# design.net
KiCad netlist of a schematic drawn in Altium Designer
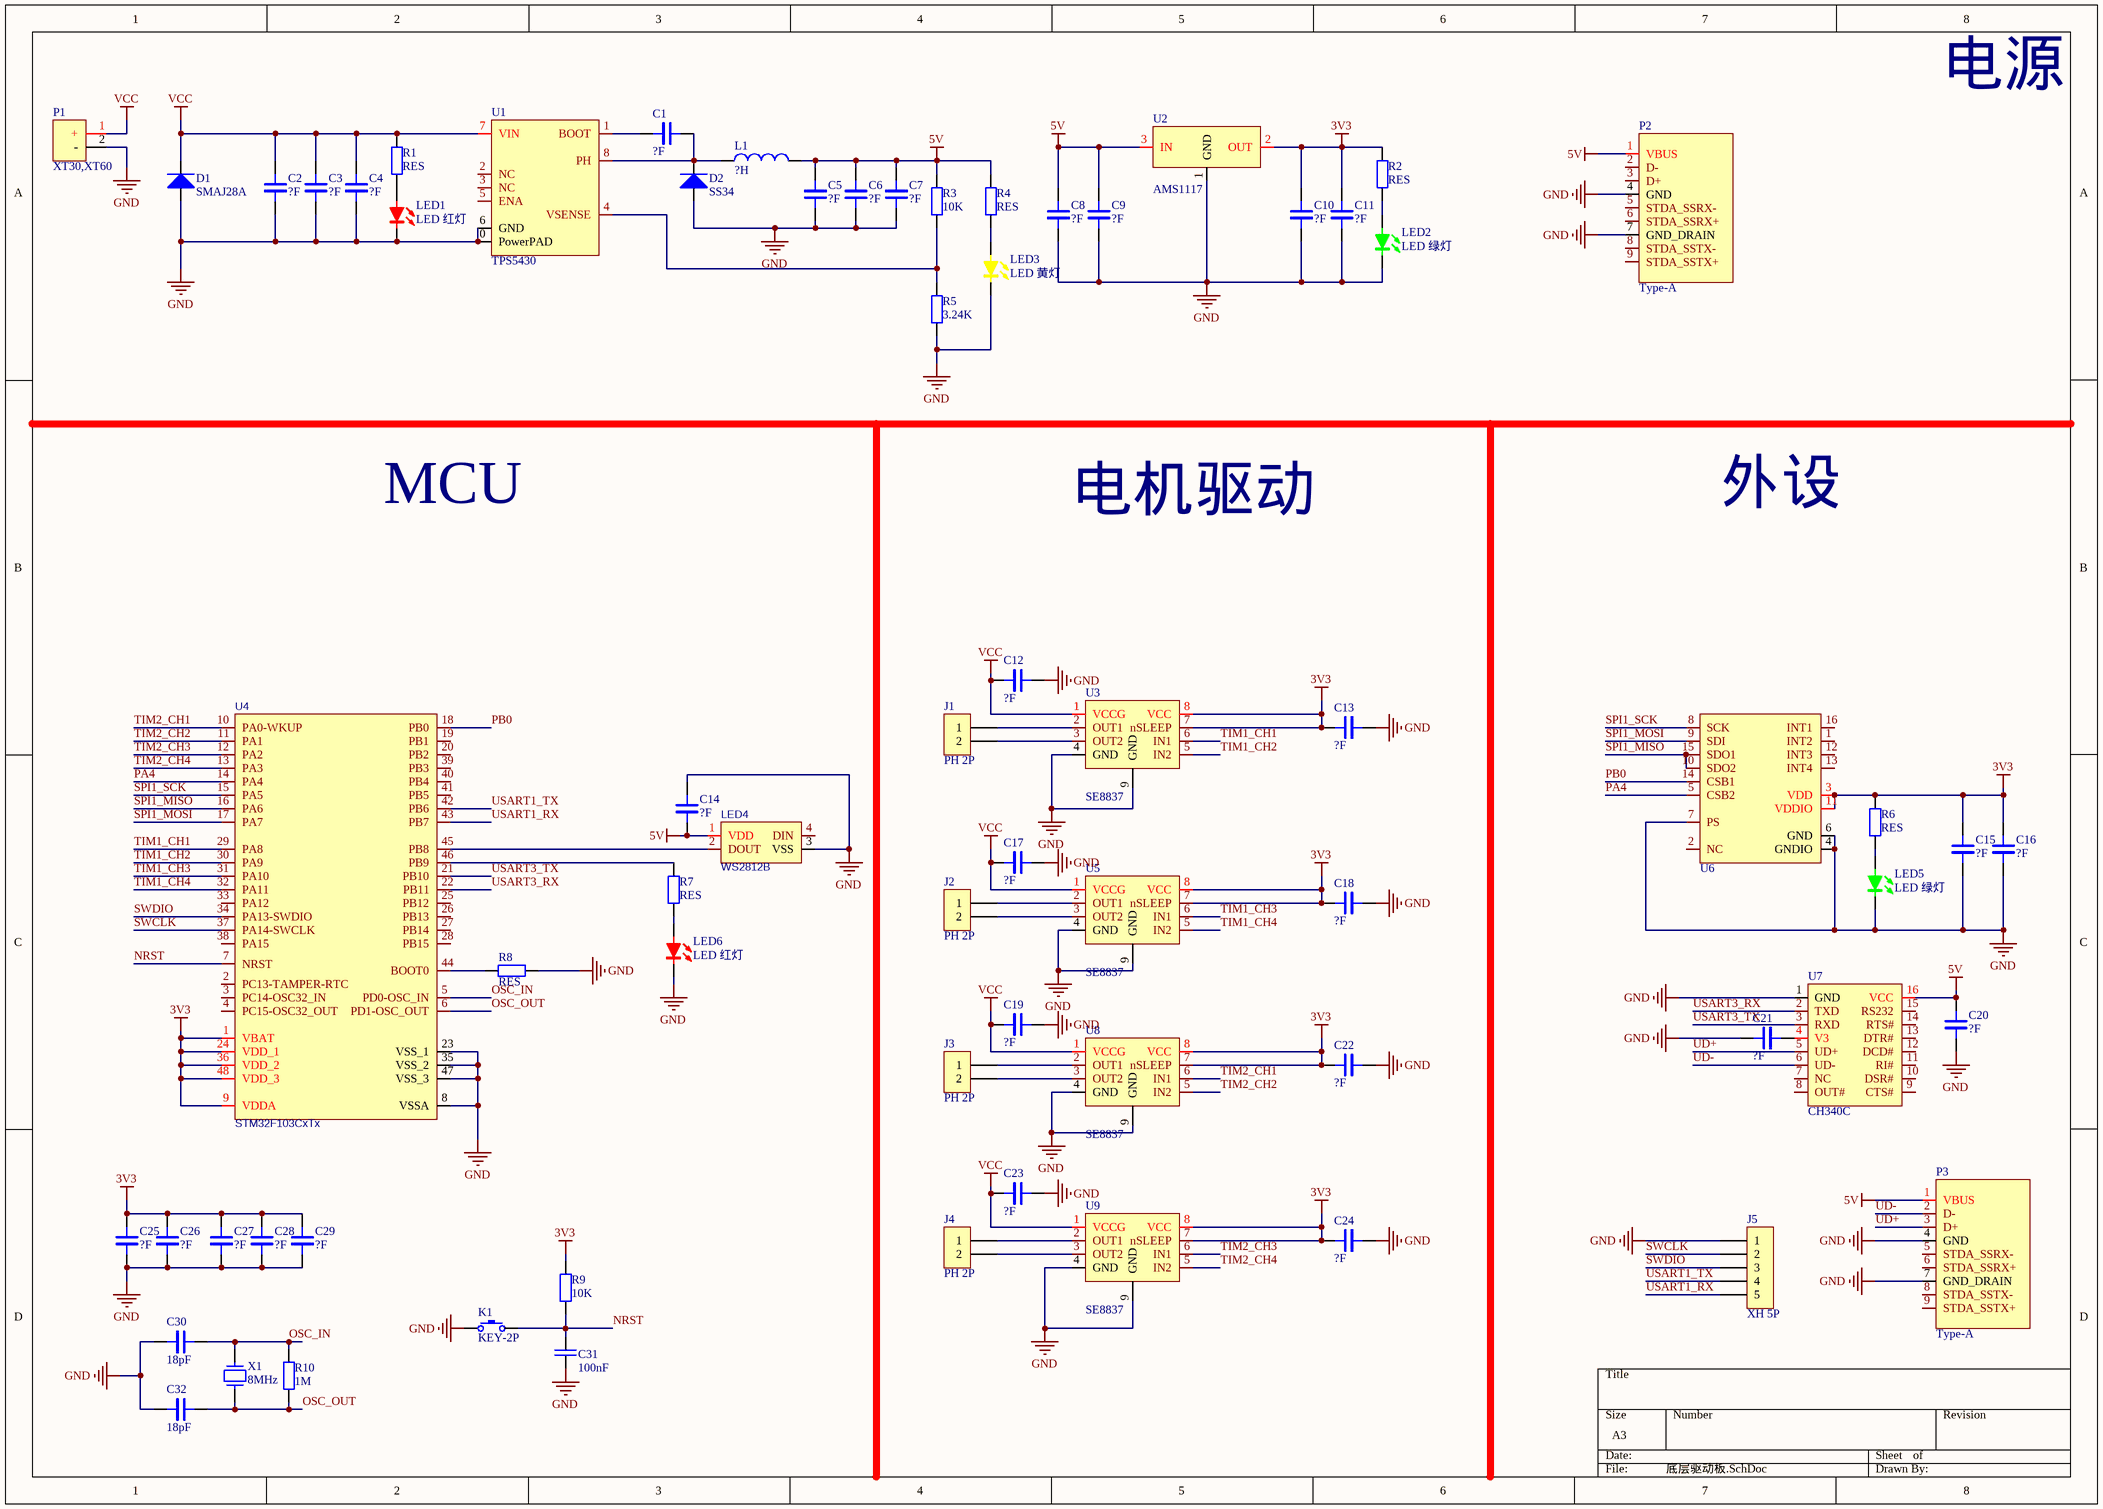
[diagram p0: 底层驱动板.SchDoc]

(export (version "E")
  (design (tool "Eeschema 10.0.6"))
  (components
    (comp (ref "C1")
      (value "?F")
      (footprint "C 0603")
      (description "Capacitor")
      (libsource (lib "General") (part "CAP"))
    )
    (comp (ref "C2")
      (value "?F")
      (footprint "C 1206")
      (description "Capacitor")
      (libsource (lib "General") (part "CAP"))
    )
    (comp (ref "C3")
      (value "?F")
      (footprint "C 1206")
      (description "Capacitor")
      (libsource (lib "General") (part "CAP"))
    )
    (comp (ref "C4")
      (value "?F")
      (footprint "C 0603")
      (description "Capacitor")
      (libsource (lib "General") (part "CAP"))
    )
    (comp (ref "C5")
      (value "?F")
      (footprint "C 1206")
      (description "Capacitor")
      (libsource (lib "General（旧）") (part "CAP"))
    )
    (comp (ref "C6")
      (value "?F")
      (footprint "C 1206")
      (description "Capacitor")
      (libsource (lib "General（旧）") (part "CAP"))
    )
    (comp (ref "C7")
      (value "?F")
      (footprint "C 0603")
      (description "Capacitor")
      (libsource (lib "General") (part "CAP"))
    )
    (comp (ref "C8")
      (value "?F")
      (footprint "C 1206")
      (description "Capacitor")
      (libsource (lib "General（旧）") (part "CAP"))
    )
    (comp (ref "C9")
      (value "?F")
      (footprint "C 1206")
      (description "Capacitor")
      (libsource (lib "General（旧）") (part "CAP"))
    )
    (comp (ref "C10")
      (value "?F")
      (footprint "C 1206")
      (description "Capacitor")
      (libsource (lib "General（旧）") (part "CAP"))
    )
    (comp (ref "C11")
      (value "?F")
      (footprint "C 1206")
      (description "Capacitor")
      (libsource (lib "General（旧）") (part "CAP"))
    )
    (comp (ref "C12")
      (value "?F")
      (footprint "C 1206")
      (description "Capacitor")
      (libsource (lib "General") (part "CAP"))
    )
    (comp (ref "C13")
      (value "?F")
      (footprint "C 0603")
      (description "Capacitor")
      (libsource (lib "General") (part "CAP"))
    )
    (comp (ref "C14")
      (value "?F")
      (footprint "C 0603")
      (description "Capacitor")
      (libsource (lib "General") (part "CAP"))
    )
    (comp (ref "C15")
      (value "?F")
      (footprint "C 0603")
      (description "Capacitor")
      (libsource (lib "General") (part "CAP"))
    )
    (comp (ref "C16")
      (value "?F")
      (footprint "C 0603")
      (description "Capacitor")
      (libsource (lib "General") (part "CAP"))
    )
    (comp (ref "C17")
      (value "?F")
      (footprint "C 1206")
      (description "Capacitor")
      (libsource (lib "General") (part "CAP"))
    )
    (comp (ref "C18")
      (value "?F")
      (footprint "C 0603")
      (description "Capacitor")
      (libsource (lib "General") (part "CAP"))
    )
    (comp (ref "C19")
      (value "?F")
      (footprint "C 1206")
      (description "Capacitor")
      (libsource (lib "General") (part "CAP"))
    )
    (comp (ref "C20")
      (value "?F")
      (footprint "C 0603")
      (description "Capacitor")
      (libsource (lib "General") (part "CAP"))
    )
    (comp (ref "C21")
      (value "?F")
      (footprint "C 0603")
      (description "Capacitor")
      (libsource (lib "General") (part "CAP"))
    )
    (comp (ref "C22")
      (value "?F")
      (footprint "C 0603")
      (description "Capacitor")
      (libsource (lib "General") (part "CAP"))
    )
    (comp (ref "C23")
      (value "?F")
      (footprint "C 1206")
      (description "Capacitor")
      (libsource (lib "General") (part "CAP"))
    )
    (comp (ref "C24")
      (value "?F")
      (footprint "C 0603")
      (description "Capacitor")
      (libsource (lib "General") (part "CAP"))
    )
    (comp (ref "C25")
      (value "?F")
      (footprint "C 0603")
      (description "Capacitor")
      (libsource (lib "General") (part "CAP"))
    )
    (comp (ref "C26")
      (value "?F")
      (footprint "C 0603")
      (description "Capacitor")
      (libsource (lib "General") (part "CAP"))
    )
    (comp (ref "C27")
      (value "?F")
      (footprint "C 0603")
      (description "Capacitor")
      (libsource (lib "General") (part "CAP"))
    )
    (comp (ref "C28")
      (value "?F")
      (footprint "C 0603")
      (description "Capacitor")
      (libsource (lib "General") (part "CAP"))
    )
    (comp (ref "C29")
      (value "?F")
      (footprint "C 0603")
      (description "Capacitor")
      (libsource (lib "General") (part "CAP"))
    )
    (comp (ref "C30")
      (value "18pF")
      (footprint "C 0603")
      (description "Capacitor")
      (libsource (lib "General") (part "CAP"))
    )
    (comp (ref "C31")
      (value "100nF")
      (footprint "C 0603")
      (fields (field (name "PUBLISHER") "Altium Limited"))
      (libsource (lib "电容-电阻-电感") (part "Cap"))
    )
    (comp (ref "C32")
      (value "18pF")
      (footprint "C 0603")
      (description "Capacitor")
      (libsource (lib "General") (part "CAP"))
    )
    (comp (ref "D1")
      (value "SMAJ28A")
      (footprint "SMA")
      (description "TVS")
      (libsource (lib "General") (part "SMAJ28A"))
    )
    (comp (ref "D2")
      (value "SS34")
      (footprint "SMA")
      (description "肖特基二极管")
      (fields
        (field (name "BOM_SUPPLIER PART") "C431540")
        (field (name "BOM_MANUFACTURER PART") "MSK12C02")
        (field (name "CONTRIBUTOR") "LCSC")
      )
      (libsource (lib "General") (part "SS34"))
    )
    (comp (ref "J1")
      (value "PH 2P")
      (footprint "PH2.0 S-W-2P")
      (description "Connector")
      (libsource (lib "General") (part "PH 2P"))
    )
    (comp (ref "J2")
      (value "PH 2P")
      (footprint "PH2.0 S-W-2P")
      (description "Connector")
      (libsource (lib "General") (part "PH 2P"))
    )
    (comp (ref "J3")
      (value "PH 2P")
      (footprint "PH2.0 S-W-2P")
      (description "Connector")
      (libsource (lib "General") (part "PH 2P"))
    )
    (comp (ref "J4")
      (value "PH 2P")
      (footprint "PH2.0 S-W-2P")
      (description "Connector")
      (libsource (lib "General") (part "PH 2P"))
    )
    (comp (ref "J5")
      (value "XH 5P")
      (footprint "XH2.54-5P_H")
      (description "Connector")
      (libsource (lib "General") (part "XH 5P"))
    )
    (comp (ref "K1")
      (value "KEY-2P")
      (footprint "*SW-按键")
      (description "Key")
      (libsource (lib "General") (part "KEY-2P"))
    )
    (comp (ref "L1")
      (value "?H")
      (footprint "SMD 7*7*4")
      (description "Inductor")
      (fields (field (name "PUBLISHER") "Altium Limited"))
      (libsource (lib "General") (part "Inductor"))
    )
    (comp (ref "LED1")
      (value "LED 红灯")
      (footprint "LED 0603-R")
      (description "LED")
      (libsource (lib "General") (part "LED 红灯"))
    )
    (comp (ref "LED2")
      (value "LED 绿灯")
      (footprint "LED 0603-G")
      (description "LED")
      (libsource (lib "General") (part "LED 绿灯"))
    )
    (comp (ref "LED3")
      (value "LED 黄灯")
      (footprint "LED 0603-Y")
      (description "LED")
      (libsource (lib "General") (part "LED 黄灯"))
    )
    (comp (ref "LED4")
      (value "WS2812B")
      (footprint "*WS2812B-3535")
      (description "可控RGB灯")
      (fields
        (field (name "BOM_MANUFACTURER PART") "WS2812B-3535")
        (field (name "BOM_SUPPLIER PART") "C114583")
        (field (name "CONTRIBUTOR") "LCSC")
      )
      (libsource (lib "General") (part "WS2812B"))
    )
    (comp (ref "LED5")
      (value "LED 绿灯")
      (footprint "LED 0603-G")
      (description "LED")
      (libsource (lib "General") (part "LED 绿灯"))
    )
    (comp (ref "LED6")
      (value "LED 红灯")
      (footprint "LED 0603-R")
      (description "LED")
      (libsource (lib "General") (part "LED 红灯"))
    )
    (comp (ref "P1")
      (value "XT30,XT60")
      (footprint "*XT30PW-M")
      (description "电源接口")
      (libsource (lib "General") (part "XT"))
    )
    (comp (ref "P2")
      (value "Type-A")
      (footprint "*Type-A 母 弯插")
      (description "USB连接器")
      (libsource (lib "General") (part "Type-A"))
    )
    (comp (ref "P3")
      (value "Type-A")
      (footprint "*Type-A 母 弯插")
      (description "USB连接器")
      (libsource (lib "General") (part "Type-A"))
    )
    (comp (ref "R1")
      (value "RES")
      (footprint "R 0603")
      (description "Resistor")
      (libsource (lib "") (part "RES_1"))
    )
    (comp (ref "R2")
      (value "RES")
      (footprint "R 0603")
      (description "Resistor")
      (libsource (lib "General（旧）") (part "RES"))
    )
    (comp (ref "R3")
      (value "10K")
      (footprint "R 0603")
      (description "Resistor")
      (libsource (lib "General（旧）") (part "RES"))
    )
    (comp (ref "R4")
      (value "RES")
      (footprint "R 0603")
      (description "Resistor")
      (libsource (lib "General（旧）") (part "RES"))
    )
    (comp (ref "R5")
      (value "3.24K")
      (footprint "R 0603")
      (description "Resistor")
      (libsource (lib "General（旧）") (part "RES"))
    )
    (comp (ref "R6")
      (value "RES")
      (footprint "R 0603")
      (description "Resistor")
      (libsource (lib "") (part "RES_1"))
    )
    (comp (ref "R7")
      (value "RES")
      (footprint "R 0603")
      (description "Resistor")
      (libsource (lib "General") (part "RES"))
    )
    (comp (ref "R8")
      (value "RES")
      (footprint "R 0603")
      (description "Resistor")
      (libsource (lib "") (part "RES_2"))
    )
    (comp (ref "R9")
      (value "10K")
      (footprint "R 0603")
      (fields (field (name "PUBLISHER") "Altium Limited"))
      (libsource (lib "电容-电阻-电感") (part "Res"))
    )
    (comp (ref "R10")
      (value "1M")
      (footprint "R 0603")
      (description "Resistor")
      (libsource (lib "General") (part "RES"))
    )
    (comp (ref "U1")
      (value "TPS5430")
      (footprint "SOP8-EP")
      (description "DC-DC 降压芯片")
      (libsource (lib "General") (part "TPS5450"))
    )
    (comp (ref "U2")
      (value "AMS1117")
      (footprint "SOT223")
      (description "LDO")
      (libsource (lib "General（旧）") (part "AMS1117"))
    )
    (comp (ref "U3")
      (value "SE8837")
      (footprint "*DFN-8-EP")
      (description "电机驱动芯片")
      (libsource (lib "General") (part "SE8837"))
    )
    (comp (ref "U4")
      (value "STM32F103CxTx")
      (footprint "LQFP48 7X7")
      (description "STM32单片机")
      (fields
        (field (name "BOM_MANUFACTURER PART") "STM32F103C8T6")
        (field (name "BOM_SUPPLIER PART") "C8734")
      )
      (libsource (lib "General") (part "STM32F103CxTx"))
    )
    (comp (ref "U5")
      (value "SE8837")
      (footprint "*DFN-8-EP")
      (description "电机驱动芯片")
      (libsource (lib "General") (part "SE8837"))
    )
    (comp (ref "U6")
      (value "BMI088")
      (footprint "*LGA-16")
      (description "陀螺仪")
      (libsource (lib "General") (part "BMI088"))
    )
    (comp (ref "U7")
      (value "CH340C")
      (footprint "SOP16")
      (description "USB转串口芯片")
      (fields
        (field (name "BOM_SUPPLIER PART") "C431540")
        (field (name "BOM_MANUFACTURER PART") "MSK12C02")
        (field (name "CONTRIBUTOR") "LCSC")
      )
      (libsource (lib "General") (part "CH340C"))
    )
    (comp (ref "U8")
      (value "SE8837")
      (footprint "*DFN-8-EP")
      (description "电机驱动芯片")
      (libsource (lib "General") (part "SE8837"))
    )
    (comp (ref "U9")
      (value "SE8837")
      (footprint "*DFN-8-EP")
      (description "电机驱动芯片")
      (libsource (lib "General") (part "SE8837"))
    )
    (comp (ref "X1")
      (value "8MHz")
      (footprint "XTAL SMD-2P")
      (description "Oscillator")
      (libsource (lib "General") (part "XTAL"))
    )
  )
  (nets
    (net (code "1") (name "/NRST") (class "Default")
      (node (ref "C31") (pin "1") (pinfunction "1_1") (pintype "passive"))
      (node (ref "K1") (pin "2") (pinfunction "2_2") (pintype "passive"))
      (node (ref "R9") (pin "1") (pinfunction "1_1") (pintype "passive"))
      (node (ref "U4") (pin "7") (pinfunction "NRST_7") (pintype "passive"))
    )
    (net (code "2") (name "/OSC_IN") (class "Default")
      (node (ref "C30") (pin "2") (pinfunction "2_2") (pintype "passive"))
      (node (ref "R10") (pin "1") (pinfunction "1_1") (pintype "passive"))
      (node (ref "U4") (pin "5") (pinfunction "PD0-OSC_IN_5") (pintype "passive"))
      (node (ref "X1") (pin "1") (pinfunction "1_1") (pintype "passive"))
    )
    (net (code "3") (name "/OSC_OUT") (class "Default")
      (node (ref "C32") (pin "2") (pinfunction "2_2") (pintype "passive"))
      (node (ref "R10") (pin "2") (pinfunction "2_2") (pintype "passive"))
      (node (ref "U4") (pin "6") (pinfunction "PD1-OSC_OUT_6") (pintype "passive"))
      (node (ref "X1") (pin "2") (pinfunction "2_2") (pintype "passive"))
    )
    (net (code "4") (name "/PA4") (class "Default")
      (node (ref "U4") (pin "14") (pinfunction "PA4_14") (pintype "passive"))
      (node (ref "U6") (pin "5") (pinfunction "CSB2_5") (pintype "passive"))
    )
    (net (code "5") (name "/PB0") (class "Default")
      (node (ref "U4") (pin "18") (pinfunction "PB0_18") (pintype "passive"))
      (node (ref "U6") (pin "14") (pinfunction "CSB1_14") (pintype "passive"))
    )
    (net (code "6") (name "/SPI1_MISO") (class "Default")
      (node (ref "U4") (pin "16") (pinfunction "PA6_16") (pintype "passive"))
      (node (ref "U6") (pin "10") (pinfunction "SDO2_10") (pintype "passive"))
      (node (ref "U6") (pin "15") (pinfunction "SDO1_15") (pintype "passive"))
    )
    (net (code "7") (name "/SPI1_MOSI") (class "Default")
      (node (ref "U4") (pin "17") (pinfunction "PA7_17") (pintype "passive"))
      (node (ref "U6") (pin "9") (pinfunction "SDI_9") (pintype "passive"))
    )
    (net (code "8") (name "/SPI1_SCK") (class "Default")
      (node (ref "U4") (pin "15") (pinfunction "PA5_15") (pintype "passive"))
      (node (ref "U6") (pin "8") (pinfunction "SCK_8") (pintype "passive"))
    )
    (net (code "9") (name "/SWCLK") (class "Default")
      (node (ref "J5") (pin "2") (pinfunction "2_2") (pintype "passive"))
      (node (ref "U4") (pin "37") (pinfunction "PA14-SWCLK_37") (pintype "passive"))
    )
    (net (code "10") (name "/SWDIO") (class "Default")
      (node (ref "J5") (pin "3") (pinfunction "3_3") (pintype "passive"))
      (node (ref "U4") (pin "34") (pinfunction "PA13-SWDIO_34") (pintype "passive"))
    )
    (net (code "11") (name "/TIM1_CH1") (class "Default")
      (node (ref "U3") (pin "6") (pinfunction "IN1_6") (pintype "passive"))
      (node (ref "U4") (pin "29") (pinfunction "PA8_29") (pintype "passive"))
    )
    (net (code "12") (name "/TIM1_CH2") (class "Default")
      (node (ref "U3") (pin "5") (pinfunction "IN2_5") (pintype "passive"))
      (node (ref "U4") (pin "30") (pinfunction "PA9_30") (pintype "passive"))
    )
    (net (code "13") (name "/TIM1_CH3") (class "Default")
      (node (ref "U4") (pin "31") (pinfunction "PA10_31") (pintype "passive"))
      (node (ref "U5") (pin "6") (pinfunction "IN1_6") (pintype "passive"))
    )
    (net (code "14") (name "/TIM1_CH4") (class "Default")
      (node (ref "U4") (pin "32") (pinfunction "PA11_32") (pintype "passive"))
      (node (ref "U5") (pin "5") (pinfunction "IN2_5") (pintype "passive"))
    )
    (net (code "15") (name "/TIM2_CH1") (class "Default")
      (node (ref "U4") (pin "10") (pinfunction "PA0-WKUP_10") (pintype "passive"))
      (node (ref "U8") (pin "6") (pinfunction "IN1_6") (pintype "passive"))
    )
    (net (code "16") (name "/TIM2_CH2") (class "Default")
      (node (ref "U4") (pin "11") (pinfunction "PA1_11") (pintype "passive"))
      (node (ref "U8") (pin "5") (pinfunction "IN2_5") (pintype "passive"))
    )
    (net (code "17") (name "/TIM2_CH3") (class "Default")
      (node (ref "U4") (pin "12") (pinfunction "PA2_12") (pintype "passive"))
      (node (ref "U9") (pin "6") (pinfunction "IN1_6") (pintype "passive"))
    )
    (net (code "18") (name "/TIM2_CH4") (class "Default")
      (node (ref "U4") (pin "13") (pinfunction "PA3_13") (pintype "passive"))
      (node (ref "U9") (pin "5") (pinfunction "IN2_5") (pintype "passive"))
    )
    (net (code "19") (name "/UD+") (class "Default")
      (node (ref "P3") (pin "3") (pinfunction "D+_3") (pintype "passive"))
      (node (ref "U7") (pin "5") (pinfunction "UD+_5") (pintype "passive"))
    )
    (net (code "20") (name "/UD-") (class "Default")
      (node (ref "P3") (pin "2") (pinfunction "D-_2") (pintype "passive"))
      (node (ref "U7") (pin "6") (pinfunction "UD-_6") (pintype "passive"))
    )
    (net (code "21") (name "/USART1_RX") (class "Default")
      (node (ref "J5") (pin "5") (pinfunction "5_5") (pintype "passive"))
      (node (ref "U4") (pin "43") (pinfunction "PB7_43") (pintype "passive"))
    )
    (net (code "22") (name "/USART1_TX") (class "Default")
      (node (ref "J5") (pin "4") (pinfunction "4_4") (pintype "passive"))
      (node (ref "U4") (pin "42") (pinfunction "PB6_42") (pintype "passive"))
    )
    (net (code "23") (name "/USART3_RX") (class "Default")
      (node (ref "U4") (pin "22") (pinfunction "PB11_22") (pintype "passive"))
      (node (ref "U7") (pin "2") (pinfunction "TXD_2") (pintype "passive"))
    )
    (net (code "24") (name "/USART3_TX") (class "Default")
      (node (ref "U4") (pin "21") (pinfunction "PB10_21") (pintype "passive"))
      (node (ref "U7") (pin "3") (pinfunction "RXD_3") (pintype "passive"))
    )
    (net (code "25") (name "3V3") (class "Default")
      (node (ref "C10") (pin "2") (pinfunction "2_2") (pintype "passive"))
      (node (ref "C11") (pin "2") (pinfunction "2_2") (pintype "passive"))
      (node (ref "C13") (pin "2") (pinfunction "2_2") (pintype "passive"))
      (node (ref "C15") (pin "2") (pinfunction "2_2") (pintype "passive"))
      (node (ref "C16") (pin "2") (pinfunction "2_2") (pintype "passive"))
      (node (ref "C18") (pin "2") (pinfunction "2_2") (pintype "passive"))
      (node (ref "C22") (pin "2") (pinfunction "2_2") (pintype "passive"))
      (node (ref "C24") (pin "2") (pinfunction "2_2") (pintype "passive"))
      (node (ref "C25") (pin "2") (pinfunction "2_2") (pintype "passive"))
      (node (ref "C26") (pin "2") (pinfunction "2_2") (pintype "passive"))
      (node (ref "C27") (pin "2") (pinfunction "2_2") (pintype "passive"))
      (node (ref "C28") (pin "2") (pinfunction "2_2") (pintype "passive"))
      (node (ref "C29") (pin "2") (pinfunction "2_2") (pintype "passive"))
      (node (ref "R2") (pin "2") (pinfunction "2_2") (pintype "passive"))
      (node (ref "R6") (pin "2") (pinfunction "2_2") (pintype "passive"))
      (node (ref "R9") (pin "2") (pinfunction "2_2") (pintype "passive"))
      (node (ref "U2") (pin "2") (pinfunction "OUT_2") (pintype "passive"))
      (node (ref "U3") (pin "7") (pinfunction "nSLEEP_7") (pintype "passive"))
      (node (ref "U3") (pin "8") (pinfunction "VCC_8") (pintype "passive"))
      (node (ref "U4") (pin "1") (pinfunction "VBAT_1") (pintype "passive"))
      (node (ref "U4") (pin "24") (pinfunction "VDD_1_24") (pintype "passive"))
      (node (ref "U4") (pin "36") (pinfunction "VDD_2_36") (pintype "passive"))
      (node (ref "U4") (pin "48") (pinfunction "VDD_3_48") (pintype "passive"))
      (node (ref "U4") (pin "9") (pinfunction "VDDA_9") (pintype "passive"))
      (node (ref "U5") (pin "7") (pinfunction "nSLEEP_7") (pintype "passive"))
      (node (ref "U5") (pin "8") (pinfunction "VCC_8") (pintype "passive"))
      (node (ref "U6") (pin "11") (pinfunction "VDDIO_11") (pintype "passive"))
      (node (ref "U6") (pin "3") (pinfunction "VDD_3") (pintype "passive"))
      (node (ref "U8") (pin "7") (pinfunction "nSLEEP_7") (pintype "passive"))
      (node (ref "U8") (pin "8") (pinfunction "VCC_8") (pintype "passive"))
      (node (ref "U9") (pin "7") (pinfunction "nSLEEP_7") (pintype "passive"))
      (node (ref "U9") (pin "8") (pinfunction "VCC_8") (pintype "passive"))
    )
    (net (code "26") (name "5V") (class "Default")
      (node (ref "C14") (pin "2") (pinfunction "2_2") (pintype "passive"))
      (node (ref "C20") (pin "2") (pinfunction "2_2") (pintype "passive"))
      (node (ref "C5") (pin "2") (pinfunction "2_2") (pintype "passive"))
      (node (ref "C6") (pin "2") (pinfunction "2_2") (pintype "passive"))
      (node (ref "C7") (pin "2") (pinfunction "2_2") (pintype "passive"))
      (node (ref "C8") (pin "2") (pinfunction "2_2") (pintype "passive"))
      (node (ref "C9") (pin "2") (pinfunction "2_2") (pintype "passive"))
      (node (ref "L1") (pin "2") (pinfunction "2_2") (pintype "passive"))
      (node (ref "LED4") (pin "1") (pinfunction "VDD_1") (pintype "passive"))
      (node (ref "P2") (pin "1") (pinfunction "VBUS_1") (pintype "passive"))
      (node (ref "P3") (pin "1") (pinfunction "VBUS_1") (pintype "passive"))
      (node (ref "R3") (pin "2") (pinfunction "2_2") (pintype "passive"))
      (node (ref "R4") (pin "2") (pinfunction "2_2") (pintype "passive"))
      (node (ref "U2") (pin "3") (pinfunction "IN_3") (pintype "passive"))
      (node (ref "U7") (pin "16") (pinfunction "VCC_16") (pintype "passive"))
    )
    (net (code "27") (name "GND") (class "Default")
      (node (ref "C10") (pin "1") (pinfunction "1_1") (pintype "passive"))
      (node (ref "C11") (pin "1") (pinfunction "1_1") (pintype "passive"))
      (node (ref "C12") (pin "1") (pinfunction "1_1") (pintype "passive"))
      (node (ref "C13") (pin "1") (pinfunction "1_1") (pintype "passive"))
      (node (ref "C14") (pin "1") (pinfunction "1_1") (pintype "passive"))
      (node (ref "C15") (pin "1") (pinfunction "1_1") (pintype "passive"))
      (node (ref "C16") (pin "1") (pinfunction "1_1") (pintype "passive"))
      (node (ref "C17") (pin "1") (pinfunction "1_1") (pintype "passive"))
      (node (ref "C18") (pin "1") (pinfunction "1_1") (pintype "passive"))
      (node (ref "C19") (pin "1") (pinfunction "1_1") (pintype "passive"))
      (node (ref "C2") (pin "1") (pinfunction "1_1") (pintype "passive"))
      (node (ref "C20") (pin "1") (pinfunction "1_1") (pintype "passive"))
      (node (ref "C21") (pin "1") (pinfunction "1_1") (pintype "passive"))
      (node (ref "C22") (pin "1") (pinfunction "1_1") (pintype "passive"))
      (node (ref "C23") (pin "1") (pinfunction "1_1") (pintype "passive"))
      (node (ref "C24") (pin "1") (pinfunction "1_1") (pintype "passive"))
      (node (ref "C25") (pin "1") (pinfunction "1_1") (pintype "passive"))
      (node (ref "C26") (pin "1") (pinfunction "1_1") (pintype "passive"))
      (node (ref "C27") (pin "1") (pinfunction "1_1") (pintype "passive"))
      (node (ref "C28") (pin "1") (pinfunction "1_1") (pintype "passive"))
      (node (ref "C29") (pin "1") (pinfunction "1_1") (pintype "passive"))
      (node (ref "C3") (pin "1") (pinfunction "1_1") (pintype "passive"))
      (node (ref "C30") (pin "1") (pinfunction "1_1") (pintype "passive"))
      (node (ref "C31") (pin "2") (pinfunction "2_2") (pintype "passive"))
      (node (ref "C32") (pin "1") (pinfunction "1_1") (pintype "passive"))
      (node (ref "C4") (pin "1") (pinfunction "1_1") (pintype "passive"))
      (node (ref "C5") (pin "1") (pinfunction "1_1") (pintype "passive"))
      (node (ref "C6") (pin "1") (pinfunction "1_1") (pintype "passive"))
      (node (ref "C7") (pin "1") (pinfunction "1_1") (pintype "passive"))
      (node (ref "C8") (pin "1") (pinfunction "1_1") (pintype "passive"))
      (node (ref "C9") (pin "1") (pinfunction "1_1") (pintype "passive"))
      (node (ref "D1") (pin "1") (pinfunction "A_1") (pintype "passive"))
      (node (ref "D2") (pin "1") (pinfunction "1_1") (pintype "passive"))
      (node (ref "J5") (pin "1") (pinfunction "1_1") (pintype "passive"))
      (node (ref "K1") (pin "1") (pinfunction "1_1") (pintype "passive"))
      (node (ref "LED1") (pin "2") (pinfunction "C_2") (pintype "passive"))
      (node (ref "LED2") (pin "2") (pinfunction "C_2") (pintype "passive"))
      (node (ref "LED3") (pin "2") (pinfunction "C_2") (pintype "passive"))
      (node (ref "LED4") (pin "3") (pinfunction "VSS_3") (pintype "passive"))
      (node (ref "LED5") (pin "2") (pinfunction "C_2") (pintype "passive"))
      (node (ref "LED6") (pin "2") (pinfunction "C_2") (pintype "passive"))
      (node (ref "P1") (pin "2") (pinfunction "-_2") (pintype "passive"))
      (node (ref "P2") (pin "4") (pinfunction "GND_4") (pintype "passive"))
      (node (ref "P2") (pin "7") (pinfunction "GND_DRAIN_7") (pintype "passive"))
      (node (ref "P3") (pin "4") (pinfunction "GND_4") (pintype "passive"))
      (node (ref "P3") (pin "7") (pinfunction "GND_DRAIN_7") (pintype "passive"))
      (node (ref "R5") (pin "1") (pinfunction "1_1") (pintype "passive"))
      (node (ref "R8") (pin "2") (pinfunction "2_2") (pintype "passive"))
      (node (ref "U1") (pin "0") (pinfunction "PowerPAD_0") (pintype "passive"))
      (node (ref "U1") (pin "6") (pinfunction "GND_6") (pintype "passive"))
      (node (ref "U2") (pin "1") (pinfunction "GND_1") (pintype "passive"))
      (node (ref "U3") (pin "4") (pinfunction "GND_4") (pintype "passive"))
      (node (ref "U3") (pin "9") (pinfunction "GND_9") (pintype "passive"))
      (node (ref "U4") (pin "23") (pinfunction "VSS_1_23") (pintype "passive"))
      (node (ref "U4") (pin "35") (pinfunction "VSS_2_35") (pintype "passive"))
      (node (ref "U4") (pin "47") (pinfunction "VSS_3_47") (pintype "passive"))
      (node (ref "U4") (pin "8") (pinfunction "VSSA_8") (pintype "passive"))
      (node (ref "U5") (pin "4") (pinfunction "GND_4") (pintype "passive"))
      (node (ref "U5") (pin "9") (pinfunction "GND_9") (pintype "passive"))
      (node (ref "U6") (pin "4") (pinfunction "GNDIO_4") (pintype "passive"))
      (node (ref "U6") (pin "6") (pinfunction "GND_6") (pintype "passive"))
      (node (ref "U6") (pin "7") (pinfunction "PS_7") (pintype "passive"))
      (node (ref "U7") (pin "1") (pinfunction "GND_1") (pintype "passive"))
      (node (ref "U8") (pin "4") (pinfunction "GND_4") (pintype "passive"))
      (node (ref "U8") (pin "9") (pinfunction "GND_9") (pintype "passive"))
      (node (ref "U9") (pin "4") (pinfunction "GND_4") (pintype "passive"))
      (node (ref "U9") (pin "9") (pinfunction "GND_9") (pintype "passive"))
    )
    (net (code "28") (name "Net-(LED1-A)") (class "Default")
      (node (ref "LED1") (pin "1") (pinfunction "A_1") (pintype "passive"))
      (node (ref "R1") (pin "1") (pinfunction "1_1") (pintype "passive"))
    )
    (net (code "29") (name "Net-(LED2-A)") (class "Default")
      (node (ref "LED2") (pin "1") (pinfunction "A_1") (pintype "passive"))
      (node (ref "R2") (pin "1") (pinfunction "1_1") (pintype "passive"))
    )
    (net (code "30") (name "Net-(LED3-A)") (class "Default")
      (node (ref "LED3") (pin "1") (pinfunction "A_1") (pintype "passive"))
      (node (ref "R4") (pin "1") (pinfunction "1_1") (pintype "passive"))
    )
    (net (code "31") (name "Net-(LED4-DOUT)") (class "Default")
      (node (ref "LED4") (pin "2") (pinfunction "DOUT_2") (pintype "passive"))
      (node (ref "U4") (pin "45") (pinfunction "PB8_45") (pintype "passive"))
    )
    (net (code "32") (name "Net-(LED5-A)") (class "Default")
      (node (ref "LED5") (pin "1") (pinfunction "A_1") (pintype "passive"))
      (node (ref "R6") (pin "1") (pinfunction "1_1") (pintype "passive"))
    )
    (net (code "33") (name "Net-(LED6-A)") (class "Default")
      (node (ref "LED6") (pin "1") (pinfunction "A_1") (pintype "passive"))
      (node (ref "R7") (pin "2") (pinfunction "2_2") (pintype "passive"))
    )
    (net (code "34") (name "Net-(U1-BOOT)") (class "Default")
      (node (ref "C1") (pin "1") (pinfunction "1_1") (pintype "passive"))
      (node (ref "U1") (pin "1") (pinfunction "BOOT_1") (pintype "passive"))
    )
    (net (code "35") (name "Net-(U1-PH)") (class "Default")
      (node (ref "C1") (pin "2") (pinfunction "2_2") (pintype "passive"))
      (node (ref "D2") (pin "2") (pinfunction "2_2") (pintype "passive"))
      (node (ref "L1") (pin "1") (pinfunction "1_1") (pintype "passive"))
      (node (ref "U1") (pin "8") (pinfunction "PH_8") (pintype "passive"))
    )
    (net (code "36") (name "Net-(U1-VSENSE)") (class "Default")
      (node (ref "R3") (pin "1") (pinfunction "1_1") (pintype "passive"))
      (node (ref "R5") (pin "2") (pinfunction "2_2") (pintype "passive"))
      (node (ref "U1") (pin "4") (pinfunction "VSENSE_4") (pintype "passive"))
    )
    (net (code "37") (name "Net-(U3-OUT1)") (class "Default")
      (node (ref "J1") (pin "1") (pinfunction "1_1") (pintype "passive"))
      (node (ref "U3") (pin "2") (pinfunction "OUT1_2") (pintype "passive"))
    )
    (net (code "38") (name "Net-(U3-OUT2)") (class "Default")
      (node (ref "J1") (pin "2") (pinfunction "2_2") (pintype "passive"))
      (node (ref "U3") (pin "3") (pinfunction "OUT2_3") (pintype "passive"))
    )
    (net (code "39") (name "Net-(U4-BOOT0)") (class "Default")
      (node (ref "R8") (pin "1") (pinfunction "1_1") (pintype "passive"))
      (node (ref "U4") (pin "44") (pinfunction "BOOT0_44") (pintype "passive"))
    )
    (net (code "40") (name "Net-(U4-PB9)") (class "Default")
      (node (ref "R7") (pin "1") (pinfunction "1_1") (pintype "passive"))
      (node (ref "U4") (pin "46") (pinfunction "PB9_46") (pintype "passive"))
    )
    (net (code "41") (name "Net-(U5-OUT1)") (class "Default")
      (node (ref "J2") (pin "1") (pinfunction "1_1") (pintype "passive"))
      (node (ref "U5") (pin "2") (pinfunction "OUT1_2") (pintype "passive"))
    )
    (net (code "42") (name "Net-(U5-OUT2)") (class "Default")
      (node (ref "J2") (pin "2") (pinfunction "2_2") (pintype "passive"))
      (node (ref "U5") (pin "3") (pinfunction "OUT2_3") (pintype "passive"))
    )
    (net (code "43") (name "Net-(U7-V3)") (class "Default")
      (node (ref "C21") (pin "2") (pinfunction "2_2") (pintype "passive"))
      (node (ref "U7") (pin "4") (pinfunction "V3_4") (pintype "passive"))
    )
    (net (code "44") (name "Net-(U8-OUT1)") (class "Default")
      (node (ref "J3") (pin "1") (pinfunction "1_1") (pintype "passive"))
      (node (ref "U8") (pin "2") (pinfunction "OUT1_2") (pintype "passive"))
    )
    (net (code "45") (name "Net-(U8-OUT2)") (class "Default")
      (node (ref "J3") (pin "2") (pinfunction "2_2") (pintype "passive"))
      (node (ref "U8") (pin "3") (pinfunction "OUT2_3") (pintype "passive"))
    )
    (net (code "46") (name "Net-(U9-OUT1)") (class "Default")
      (node (ref "J4") (pin "1") (pinfunction "1_1") (pintype "passive"))
      (node (ref "U9") (pin "2") (pinfunction "OUT1_2") (pintype "passive"))
    )
    (net (code "47") (name "Net-(U9-OUT2)") (class "Default")
      (node (ref "J4") (pin "2") (pinfunction "2_2") (pintype "passive"))
      (node (ref "U9") (pin "3") (pinfunction "OUT2_3") (pintype "passive"))
    )
    (net (code "48") (name "VCC") (class "Default")
      (node (ref "C12") (pin "2") (pinfunction "2_2") (pintype "passive"))
      (node (ref "C17") (pin "2") (pinfunction "2_2") (pintype "passive"))
      (node (ref "C19") (pin "2") (pinfunction "2_2") (pintype "passive"))
      (node (ref "C2") (pin "2") (pinfunction "2_2") (pintype "passive"))
      (node (ref "C23") (pin "2") (pinfunction "2_2") (pintype "passive"))
      (node (ref "C3") (pin "2") (pinfunction "2_2") (pintype "passive"))
      (node (ref "C4") (pin "2") (pinfunction "2_2") (pintype "passive"))
      (node (ref "D1") (pin "2") (pinfunction "K_2") (pintype "passive"))
      (node (ref "P1") (pin "1") (pinfunction "+_1") (pintype "passive"))
      (node (ref "R1") (pin "2") (pinfunction "2_2") (pintype "passive"))
      (node (ref "U1") (pin "7") (pinfunction "VIN_7") (pintype "passive"))
      (node (ref "U3") (pin "1") (pinfunction "VCCG_1") (pintype "passive"))
      (node (ref "U5") (pin "1") (pinfunction "VCCG_1") (pintype "passive"))
      (node (ref "U8") (pin "1") (pinfunction "VCCG_1") (pintype "passive"))
      (node (ref "U9") (pin "1") (pinfunction "VCCG_1") (pintype "passive"))
    )
    (net (code "49") (name "unconnected-(LED4-DIN-Pad4)") (class "Default")
      (node (ref "LED4") (pin "4") (pinfunction "DIN_4") (pintype "passive"))
    )
    (net (code "50") (name "unconnected-(P2-D+-Pad3)") (class "Default")
      (node (ref "P2") (pin "3") (pinfunction "D+_3") (pintype "passive"))
    )
    (net (code "51") (name "unconnected-(P2-D--Pad2)") (class "Default")
      (node (ref "P2") (pin "2") (pinfunction "D-_2") (pintype "passive"))
    )
    (net (code "52") (name "unconnected-(P2-STDA_SSRX+-Pad6)") (class "Default")
      (node (ref "P2") (pin "6") (pinfunction "STDA_SSRX+_6") (pintype "passive"))
    )
    (net (code "53") (name "unconnected-(P2-STDA_SSRX--Pad5)") (class "Default")
      (node (ref "P2") (pin "5") (pinfunction "STDA_SSRX-_5") (pintype "passive"))
    )
    (net (code "54") (name "unconnected-(P2-STDA_SSTX+-Pad9)") (class "Default")
      (node (ref "P2") (pin "9") (pinfunction "STDA_SSTX+_9") (pintype "passive"))
    )
    (net (code "55") (name "unconnected-(P2-STDA_SSTX--Pad8)") (class "Default")
      (node (ref "P2") (pin "8") (pinfunction "STDA_SSTX-_8") (pintype "passive"))
    )
    (net (code "56") (name "unconnected-(P3-STDA_SSRX+-Pad6)") (class "Default")
      (node (ref "P3") (pin "6") (pinfunction "STDA_SSRX+_6") (pintype "passive"))
    )
    (net (code "57") (name "unconnected-(P3-STDA_SSRX--Pad5)") (class "Default")
      (node (ref "P3") (pin "5") (pinfunction "STDA_SSRX-_5") (pintype "passive"))
    )
    (net (code "58") (name "unconnected-(P3-STDA_SSTX+-Pad9)") (class "Default")
      (node (ref "P3") (pin "9") (pinfunction "STDA_SSTX+_9") (pintype "passive"))
    )
    (net (code "59") (name "unconnected-(P3-STDA_SSTX--Pad8)") (class "Default")
      (node (ref "P3") (pin "8") (pinfunction "STDA_SSTX-_8") (pintype "passive"))
    )
    (net (code "60") (name "unconnected-(U1-ENA-Pad5)") (class "Default")
      (node (ref "U1") (pin "5") (pinfunction "ENA_5") (pintype "passive"))
    )
    (net (code "61") (name "unconnected-(U1-NC-Pad2)") (class "Default")
      (node (ref "U1") (pin "2") (pinfunction "NC_2") (pintype "passive"))
    )
    (net (code "62") (name "unconnected-(U1-NC-Pad3)") (class "Default")
      (node (ref "U1") (pin "3") (pinfunction "NC_3") (pintype "passive"))
    )
    (net (code "63") (name "unconnected-(U4-PA12-Pad33)") (class "Default")
      (node (ref "U4") (pin "33") (pinfunction "PA12_33") (pintype "passive"))
    )
    (net (code "64") (name "unconnected-(U4-PA15-Pad38)") (class "Default")
      (node (ref "U4") (pin "38") (pinfunction "PA15_38") (pintype "passive"))
    )
    (net (code "65") (name "unconnected-(U4-PB1-Pad19)") (class "Default")
      (node (ref "U4") (pin "19") (pinfunction "PB1_19") (pintype "passive"))
    )
    (net (code "66") (name "unconnected-(U4-PB2-Pad20)") (class "Default")
      (node (ref "U4") (pin "20") (pinfunction "PB2_20") (pintype "passive"))
    )
    (net (code "67") (name "unconnected-(U4-PB3-Pad39)") (class "Default")
      (node (ref "U4") (pin "39") (pinfunction "PB3_39") (pintype "passive"))
    )
    (net (code "68") (name "unconnected-(U4-PB4-Pad40)") (class "Default")
      (node (ref "U4") (pin "40") (pinfunction "PB4_40") (pintype "passive"))
    )
    (net (code "69") (name "unconnected-(U4-PB5-Pad41)") (class "Default")
      (node (ref "U4") (pin "41") (pinfunction "PB5_41") (pintype "passive"))
    )
    (net (code "70") (name "unconnected-(U4-PB12-Pad25)") (class "Default")
      (node (ref "U4") (pin "25") (pinfunction "PB12_25") (pintype "passive"))
    )
    (net (code "71") (name "unconnected-(U4-PB13-Pad26)") (class "Default")
      (node (ref "U4") (pin "26") (pinfunction "PB13_26") (pintype "passive"))
    )
    (net (code "72") (name "unconnected-(U4-PB14-Pad27)") (class "Default")
      (node (ref "U4") (pin "27") (pinfunction "PB14_27") (pintype "passive"))
    )
    (net (code "73") (name "unconnected-(U4-PB15-Pad28)") (class "Default")
      (node (ref "U4") (pin "28") (pinfunction "PB15_28") (pintype "passive"))
    )
    (net (code "74") (name "unconnected-(U4-PC13-TAMPER-RTC-Pad2)") (class "Default")
      (node (ref "U4") (pin "2") (pinfunction "PC13-TAMPER-RTC_2") (pintype "passive"))
    )
    (net (code "75") (name "unconnected-(U4-PC14-OSC32_IN-Pad3)") (class "Default")
      (node (ref "U4") (pin "3") (pinfunction "PC14-OSC32_IN_3") (pintype "passive"))
    )
    (net (code "76") (name "unconnected-(U4-PC15-OSC32_OUT-Pad4)") (class "Default")
      (node (ref "U4") (pin "4") (pinfunction "PC15-OSC32_OUT_4") (pintype "passive"))
    )
    (net (code "77") (name "unconnected-(U6-INT1-Pad16)") (class "Default")
      (node (ref "U6") (pin "16") (pinfunction "INT1_16") (pintype "passive"))
    )
    (net (code "78") (name "unconnected-(U6-INT2-Pad1)") (class "Default")
      (node (ref "U6") (pin "1") (pinfunction "INT2_1") (pintype "passive"))
    )
    (net (code "79") (name "unconnected-(U6-INT3-Pad12)") (class "Default")
      (node (ref "U6") (pin "12") (pinfunction "INT3_12") (pintype "passive"))
    )
    (net (code "80") (name "unconnected-(U6-INT4-Pad13)") (class "Default")
      (node (ref "U6") (pin "13") (pinfunction "INT4_13") (pintype "passive"))
    )
    (net (code "81") (name "unconnected-(U6-NC-Pad2)") (class "Default")
      (node (ref "U6") (pin "2") (pinfunction "NC_2") (pintype "passive"))
    )
    (net (code "82") (name "unconnected-(U7-CTS#-Pad9)") (class "Default")
      (node (ref "U7") (pin "9") (pinfunction "CTS#_9") (pintype "passive"))
    )
    (net (code "83") (name "unconnected-(U7-DCD#-Pad12)") (class "Default")
      (node (ref "U7") (pin "12") (pinfunction "DCD#_12") (pintype "passive"))
    )
    (net (code "84") (name "unconnected-(U7-DSR#-Pad10)") (class "Default")
      (node (ref "U7") (pin "10") (pinfunction "DSR#_10") (pintype "passive"))
    )
    (net (code "85") (name "unconnected-(U7-DTR#-Pad13)") (class "Default")
      (node (ref "U7") (pin "13") (pinfunction "DTR#_13") (pintype "passive"))
    )
    (net (code "86") (name "unconnected-(U7-NC-Pad7)") (class "Default")
      (node (ref "U7") (pin "7") (pinfunction "NC_7") (pintype "passive"))
    )
    (net (code "87") (name "unconnected-(U7-OUT#-Pad8)") (class "Default")
      (node (ref "U7") (pin "8") (pinfunction "OUT#_8") (pintype "passive"))
    )
    (net (code "88") (name "unconnected-(U7-RI#-Pad11)") (class "Default")
      (node (ref "U7") (pin "11") (pinfunction "RI#_11") (pintype "passive"))
    )
    (net (code "89") (name "unconnected-(U7-RS232-Pad15)") (class "Default")
      (node (ref "U7") (pin "15") (pinfunction "RS232_15") (pintype "passive"))
    )
    (net (code "90") (name "unconnected-(U7-RTS#-Pad14)") (class "Default")
      (node (ref "U7") (pin "14") (pinfunction "RTS#_14") (pintype "passive"))
    )
  )
)
